# USB_To_UART.net
KiCad netlist of a schematic drawn in Altium Designer
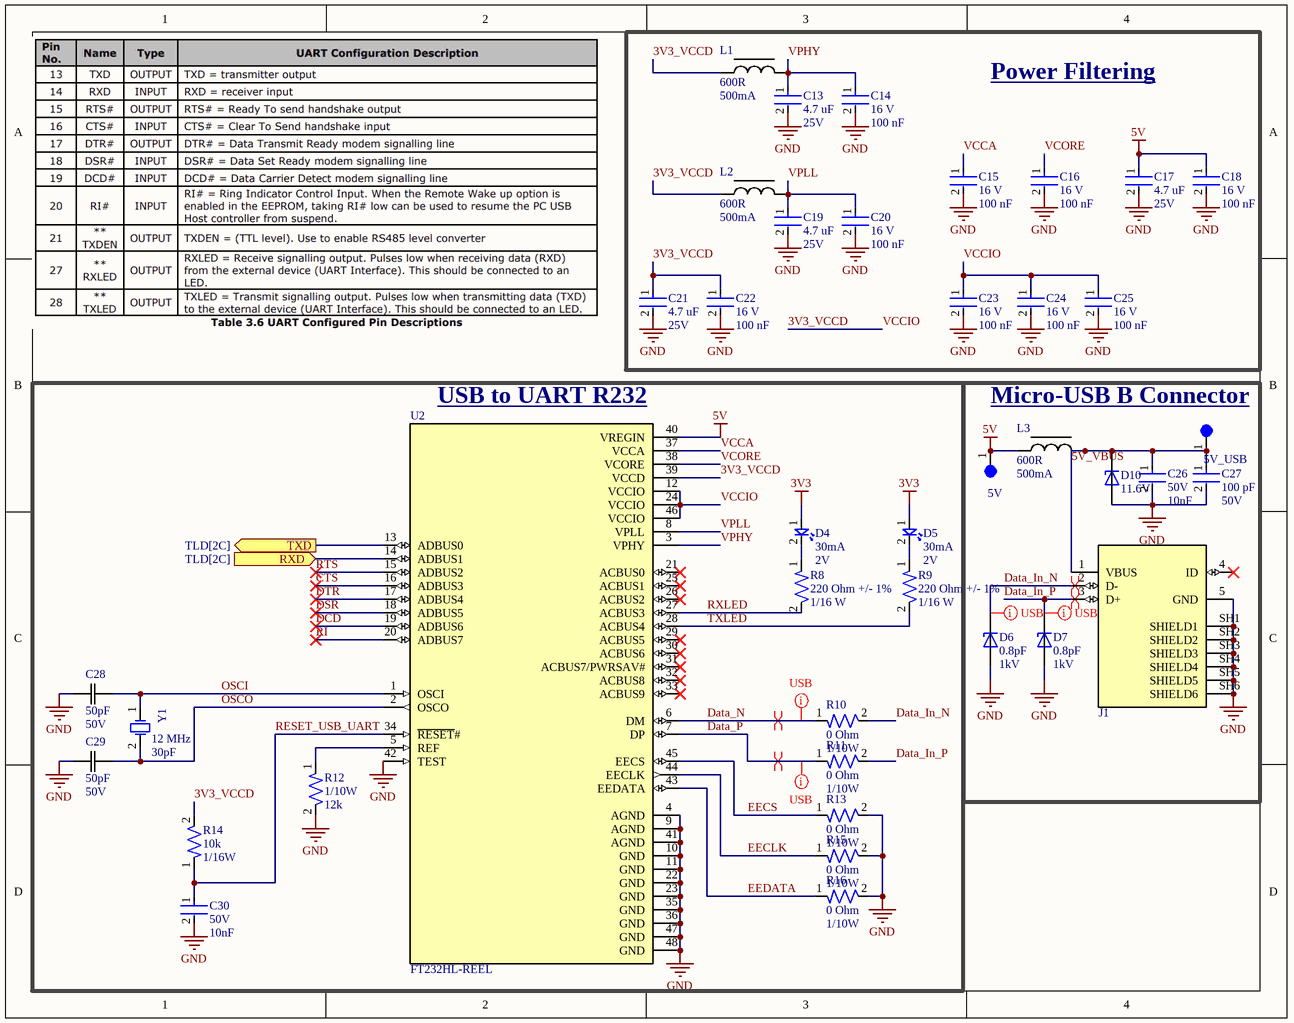
[diagram p0: USB_To_UART.SchDoc]

(export (version "E")
  (design (tool "Eeschema 10.0.6"))
  (components
    (comp (ref "5V")
      (value "5003")
      (footprint "TEST-POINT-0001")
      (description "Oranange PC Test Point, Miniature Phoisphor Bronze Silver Plating Through Hole Mounting Type")
      (libsource (lib "JLC_25") (part "TEST-POINT-0001"))
    )
    (comp (ref "5V_USB")
      (value "5003")
      (footprint "TEST-POINT-0001")
      (description "Oranange PC Test Point, Miniature Phoisphor Bronze Silver Plating Through Hole Mounting Type")
      (libsource (lib "JLC_25") (part "TEST-POINT-0001"))
    )
    (comp (ref "C13")
      (value "CC0603KRX5R8BB475")
      (footprint "CAP-0603")
      (description "CAP CER 4.7UF 25V X5R 0603")
      (fields (field (name "CAPACITANCE") "4.7 uF") (field (name "VOLTAGE") "25V"))
      (libsource (lib "JLC_25") (part "CAP-4.7U-0001"))
    )
    (comp (ref "C14")
      (value "CC0402KRX7R7BB104")
      (footprint "CAP-0402")
      (description "CAP CER 0.1UF 16V X7R 0402")
      (fields (field (name "VOLTAGE RATING") "16 V") (field (name "CAPACITANCE") "100 nF"))
      (libsource (lib "JLC_25") (part "CAP-0.1U-0001"))
    )
    (comp (ref "C15")
      (value "CC0402KRX7R7BB104")
      (footprint "CAP-0402")
      (description "CAP CER 0.1UF 16V X7R 0402")
      (fields (field (name "VOLTAGE RATING") "16 V") (field (name "CAPACITANCE") "100 nF"))
      (libsource (lib "JLC_25") (part "CAP-0.1U-0001"))
    )
    (comp (ref "C16")
      (value "CC0402KRX7R7BB104")
      (footprint "CAP-0402")
      (description "CAP CER 0.1UF 16V X7R 0402")
      (fields (field (name "VOLTAGE RATING") "16 V") (field (name "CAPACITANCE") "100 nF"))
      (libsource (lib "JLC_25") (part "CAP-0.1U-0001"))
    )
    (comp (ref "C17")
      (value "CC0603KRX5R8BB475")
      (footprint "CAP-0603")
      (description "CAP CER 4.7UF 25V X5R 0603")
      (fields (field (name "CAPACITANCE") "4.7 uF") (field (name "VOLTAGE") "25V"))
      (libsource (lib "JLC_25") (part "CAP-4.7U-0001"))
    )
    (comp (ref "C18")
      (value "CC0402KRX7R7BB104")
      (footprint "CAP-0402")
      (description "CAP CER 0.1UF 16V X7R 0402")
      (fields (field (name "VOLTAGE RATING") "16 V") (field (name "CAPACITANCE") "100 nF"))
      (libsource (lib "JLC_25") (part "CAP-0.1U-0001"))
    )
    (comp (ref "C19")
      (value "CC0603KRX5R8BB475")
      (footprint "CAP-0603")
      (description "CAP CER 4.7UF 25V X5R 0603")
      (fields (field (name "CAPACITANCE") "4.7 uF") (field (name "VOLTAGE") "25V"))
      (libsource (lib "JLC_25") (part "CAP-4.7U-0001"))
    )
    (comp (ref "C20")
      (value "CC0402KRX7R7BB104")
      (footprint "CAP-0402")
      (description "CAP CER 0.1UF 16V X7R 0402")
      (fields (field (name "VOLTAGE RATING") "16 V") (field (name "CAPACITANCE") "100 nF"))
      (libsource (lib "JLC_25") (part "CAP-0.1U-0001"))
    )
    (comp (ref "C21")
      (value "CC0603KRX5R8BB475")
      (footprint "CAP-0603")
      (description "CAP CER 4.7UF 25V X5R 0603")
      (fields (field (name "CAPACITANCE") "4.7 uF") (field (name "VOLTAGE") "25V"))
      (libsource (lib "JLC_25") (part "CAP-4.7U-0001"))
    )
    (comp (ref "C22")
      (value "CC0402KRX7R7BB104")
      (footprint "CAP-0402")
      (description "CAP CER 0.1UF 16V X7R 0402")
      (fields (field (name "VOLTAGE RATING") "16 V") (field (name "CAPACITANCE") "100 nF"))
      (libsource (lib "JLC_25") (part "CAP-0.1U-0001"))
    )
    (comp (ref "C23")
      (value "CC0402KRX7R7BB104")
      (footprint "CAP-0402")
      (description "CAP CER 0.1UF 16V X7R 0402")
      (fields (field (name "VOLTAGE RATING") "16 V") (field (name "CAPACITANCE") "100 nF"))
      (libsource (lib "JLC_25") (part "CAP-0.1U-0001"))
    )
    (comp (ref "C24")
      (value "CC0402KRX7R7BB104")
      (footprint "CAP-0402")
      (description "CAP CER 0.1UF 16V X7R 0402")
      (fields (field (name "VOLTAGE RATING") "16 V") (field (name "CAPACITANCE") "100 nF"))
      (libsource (lib "JLC_25") (part "CAP-0.1U-0001"))
    )
    (comp (ref "C25")
      (value "CC0402KRX7R7BB104")
      (footprint "CAP-0402")
      (description "CAP CER 0.1UF 16V X7R 0402")
      (fields (field (name "VOLTAGE RATING") "16 V") (field (name "CAPACITANCE") "100 nF"))
      (libsource (lib "JLC_25") (part "CAP-0.1U-0001"))
    )
    (comp (ref "C26")
      (value "GRM2195C1H103JA01D")
      (footprint "CAP-0805")
      (description "CAP CER 10000PF 50V C0G/NP0 0805")
      (fields (field (name "VOLTAGE") "50V") (field (name "CAPACITANCE") "10nF"))
      (libsource (lib "JLC_25") (part "CAP-10N-0001"))
    )
    (comp (ref "C27")
      (value "CC0402JRNPO9BN101")
      (footprint "CAP-0402")
      (description "CAP CER 100PF 50V C0G/NPO 0402")
      (fields (field (name "CAPACITANCE") "100 pF") (field (name "VOLTAGE") "50V"))
      (libsource (lib "JLC_25") (part "CAP-100P-0001"))
    )
    (comp (ref "C28")
      (value "CC0402JRNPO9BN500")
      (footprint "CAP_CC0402_YAG")
      (description "50 pF ±5% 50V Ceramic Capacitor C0G, NP0 0402 (1005 Metric)")
      (fields
        (field (name "CAPACITANCE") "50pF")
        (field (name "VOLTAGE") "50V")
        (field (name "COPYRIGHT") "Copyright (C) 2025 Ultra Librarian. All rights reserved.")
      )
      (libsource (lib "MasterLib") (part "CAP-50p"))
    )
    (comp (ref "C29")
      (value "CC0402JRNPO9BN500")
      (footprint "CAP_CC0402_YAG")
      (description "50 pF ±5% 50V Ceramic Capacitor C0G, NP0 0402 (1005 Metric)")
      (fields
        (field (name "CAPACITANCE") "50pF")
        (field (name "VOLTAGE") "50V")
        (field (name "COPYRIGHT") "Copyright (C) 2025 Ultra Librarian. All rights reserved.")
      )
      (libsource (lib "MasterLib") (part "CAP-50p"))
    )
    (comp (ref "C30")
      (value "GRM2195C1H103JA01D")
      (footprint "CAP-0805")
      (description "CAP CER 10000PF 50V C0G/NP0 0805")
      (fields (field (name "VOLTAGE") "50V") (field (name "CAPACITANCE") "10nF"))
      (libsource (lib "JLC_25") (part "CAP-10N-0001"))
    )
    (comp (ref "D4")
      (value "BL-HKC36G-AV-TRB")
      (footprint "LED-0603")
      (description "LED YELLOW CLEAR 0603 SMD")
      (fields (field (name "FORWARD CURRENT") "30mA") (field (name "FORWARD VOLTAGE") "2V"))
      (libsource (lib "JLC_25") (part "LED-0001"))
    )
    (comp (ref "D5")
      (value "BL-HKC36G-AV-TRB")
      (footprint "LED-0603")
      (description "LED YELLOW CLEAR 0603 SMD")
      (fields (field (name "FORWARD CURRENT") "30mA") (field (name "FORWARD VOLTAGE") "2V"))
      (libsource (lib "JLC_25") (part "LED-0001"))
    )
    (comp (ref "D6")
      (value "ESD321DPYR")
      (footprint "TVS_ESD321DPYR")
      (description "0.8-pF 3.3-V Â±30-kV ESD protection diode with 6.8-V 16-A TLP clamping in 0402 package for USB 2.0")
      (fields
        (field (name "MF") "Texas Instruments")
        (field (name "CAPACITANCE") "0.8pF")
        (field (name "VOLTAGE") "1kV")
      )
      (libsource (lib "JLC_25") (part "DIO-TVS-0004"))
    )
    (comp (ref "D7")
      (value "ESD321DPYR")
      (footprint "TVS_ESD321DPYR")
      (description "0.8-pF 3.3-V Â±30-kV ESD protection diode with 6.8-V 16-A TLP clamping in 0402 package for USB 2.0")
      (fields
        (field (name "MF") "Texas Instruments")
        (field (name "CAPACITANCE") "0.8pF")
        (field (name "VOLTAGE") "1kV")
      )
      (libsource (lib "JLC_25") (part "DIO-TVS-0004"))
    )
    (comp (ref "D10")
      (value "ESDA7P60-1U1M")
      (footprint "TVS_ESDA7P60-1U1M")
      (description "TVS DIODE 5VWM 11.6VC 1610")
      (fields (field (name "MF") "{'manufacturer': u'STMicroelectronics'}") (field (name "VOLTAGE") "11.6V"))
      (libsource (lib "MasterLib") (part "DIO-TVS-11V"))
    )
    (comp (ref "J1")
      (value "1050170001")
      (footprint "MOLEX_1050170001")
      (description "USB - micro B USB 2.0 Receptacle Connector 5 Position Surface Mount, Right Angle; Through Hole")
      (fields (field (name "MF") "Molex"))
      (libsource (lib "JLC_25") (part "CONN-Micro-USB-B-0001"))
    )
    (comp (ref "L1")
      (value "BLM18AG601SN1D")
      (footprint "FILTER_BLM18AG_MUR-L")
      (description "600 Ohms @ 100 MHz 1 Ferrite Bead 0603 (1608 Metric) 500mA 380mOhm")
      (fields
        (field (name "RESISTANCE") "600R")
        (field (name "CURRENT") "500mA")
        (field (name "COPYRIGHT") "Copyright (C) 2025 Ultra Librarian. All rights reserved.")
      )
      (libsource (lib "JLC_25") (part "FBEAD-600R-0.5A"))
    )
    (comp (ref "L2")
      (value "BLM18AG601SN1D")
      (footprint "FILTER_BLM18AG_MUR-L")
      (description "600 Ohms @ 100 MHz 1 Ferrite Bead 0603 (1608 Metric) 500mA 380mOhm")
      (fields
        (field (name "RESISTANCE") "600R")
        (field (name "CURRENT") "500mA")
        (field (name "COPYRIGHT") "Copyright (C) 2025 Ultra Librarian. All rights reserved.")
      )
      (libsource (lib "JLC_25") (part "FBEAD-600R-0.5A"))
    )
    (comp (ref "L3")
      (value "BLM18AG601SN1D")
      (footprint "FILTER_BLM18AG_MUR-L")
      (description "600 Ohms @ 100 MHz 1 Ferrite Bead 0603 (1608 Metric) 500mA 380mOhm")
      (fields
        (field (name "RESISTANCE") "600R")
        (field (name "CURRENT") "500mA")
        (field (name "COPYRIGHT") "Copyright (C) 2025 Ultra Librarian. All rights reserved.")
      )
      (libsource (lib "JLC_25") (part "FBEAD-600R-0.5A"))
    )
    (comp (ref "R8")
      (value "RM04FTN2200")
      (footprint "RES-0402")
      (fields
        (field (name "JLC PART NUMBER") "C160487")
        (field (name "RESISTANCE") "220 Ohm +/- 1%")
        (field (name "POWER") "1/16 W")
      )
      (libsource (lib "MasterLib") (part "RES-220-0002-JLC"))
    )
    (comp (ref "R9")
      (value "RM04FTN2200")
      (footprint "RES-0402")
      (fields
        (field (name "JLC PART NUMBER") "C160487")
        (field (name "RESISTANCE") "220 Ohm +/- 1%")
        (field (name "POWER") "1/16 W")
      )
      (libsource (lib "MasterLib") (part "RES-220-0002-JLC"))
    )
    (comp (ref "R10")
      (value "RESC1607X60N")
      (footprint "RESC1607X60N")
      (description "0 Ohms Jumper Chip Resistor 0603 (1608 Metric) Moisture Resistant Thick Film")
      (fields
        (field (name "JLC PART NUMBER") "C106231")
        (field (name "RESISTANCE") "0 Ohm")
        (field (name "POWER") "1/10W")
      )
      (libsource (lib "MasterLib") (part "RES-0-0003"))
    )
    (comp (ref "R11")
      (value "RESC1607X60N")
      (footprint "RESC1607X60N")
      (description "0 Ohms Jumper Chip Resistor 0603 (1608 Metric) Moisture Resistant Thick Film")
      (fields
        (field (name "JLC PART NUMBER") "C106231")
        (field (name "RESISTANCE") "0 Ohm")
        (field (name "POWER") "1/10W")
      )
      (libsource (lib "MasterLib") (part "RES-0-0003"))
    )
    (comp (ref "R12")
      (value "RC0603FR-0712KL")
      (footprint "RES-0603")
      (description "RES 12K OHM 1% 1/10W 0603")
      (fields
        (field (name "TOLERANCE") "1%")
        (field (name "POWER") "1/10W")
        (field (name "RESISTANCE") "12k")
      )
      (libsource (lib "JLC_25") (part "RES-12k-0001"))
    )
    (comp (ref "R13")
      (value "RESC1607X60N")
      (footprint "RESC1607X60N")
      (description "0 Ohms Jumper Chip Resistor 0603 (1608 Metric) Moisture Resistant Thick Film")
      (fields
        (field (name "JLC PART NUMBER") "C106231")
        (field (name "RESISTANCE") "0 Ohm")
        (field (name "POWER") "1/10W")
      )
      (libsource (lib "MasterLib") (part "RES-0-0003"))
    )
    (comp (ref "R14")
      (value "RC0402FR-0710KL")
      (footprint "RES-0402")
      (description "RES 10K OHM 1% 1/16W 0402")
      (fields
        (field (name "TOLERANCE") "1%")
        (field (name "RESISTANCE") "10k")
        (field (name "POWER") "1/16W")
      )
      (libsource (lib "JLC_25") (part "RES-10k-0001"))
    )
    (comp (ref "R15")
      (value "RESC1607X60N")
      (footprint "RESC1607X60N")
      (description "0 Ohms Jumper Chip Resistor 0603 (1608 Metric) Moisture Resistant Thick Film")
      (fields
        (field (name "JLC PART NUMBER") "C106231")
        (field (name "RESISTANCE") "0 Ohm")
        (field (name "POWER") "1/10W")
      )
      (libsource (lib "MasterLib") (part "RES-0-0003"))
    )
    (comp (ref "R16")
      (value "RESC1607X60N")
      (footprint "RESC1607X60N")
      (description "0 Ohms Jumper Chip Resistor 0603 (1608 Metric) Moisture Resistant Thick Film")
      (fields
        (field (name "JLC PART NUMBER") "C106231")
        (field (name "RESISTANCE") "0 Ohm")
        (field (name "POWER") "1/10W")
      )
      (libsource (lib "MasterLib") (part "RES-0-0003"))
    )
    (comp (ref "U2")
      (value "FT232HL-REEL")
      (footprint "QFP50P900X900X160-48N")
      (description "Ic, Interface; Usb Hi-Speed To Uart/Fifo/Spi/Jtag, I2c; 1.8v-5.25v; 25ma; Lqfp-48")
      (fields (field (name "MF") "FTDI, Future"))
      (libsource (lib "JLC_25") (part "IC-USB-TO_UART"))
    )
    (comp (ref "Y1")
      (value "830010043")
      (footprint "WE-XTAL_HC49/4HSMX")
      (description "WE-XTAL Quartz Crystal, SMT, HC49/4HSMX, 12 MHz, ±30ppm")
      (fields
        (field (name "MANUFACTURER") "Wurth Elektronik")
        (field (name "FREQUENCY") "12 MHz")
        (field (name "LOAD CAPACITANCE") "30pF")
      )
      (libsource (lib "MasterLib") (part "CRYSTAL-12MHz-30pF"))
    )
  )
  (nets
    (net (code "1") (name "/3V3_VCCD") (class "Default")
      (node (ref "C21") (pin "1") (pinfunction "1_1") (pintype "passive"))
      (node (ref "C22") (pin "1") (pinfunction "1_1") (pintype "passive"))
      (node (ref "C23") (pin "1") (pinfunction "1_1") (pintype "passive"))
      (node (ref "C24") (pin "1") (pinfunction "1_1") (pintype "passive"))
      (node (ref "C25") (pin "1") (pinfunction "1_1") (pintype "passive"))
      (node (ref "L1") (pin "1") (pinfunction "1_1") (pintype "passive"))
      (node (ref "L2") (pin "1") (pinfunction "1_1") (pintype "passive"))
      (node (ref "R14") (pin "2") (pinfunction "2_2") (pintype "passive"))
      (node (ref "U2") (pin "12") (pinfunction "VCCIO_12") (pintype "power_in"))
      (node (ref "U2") (pin "24") (pinfunction "VCCIO_24") (pintype "power_in"))
      (node (ref "U2") (pin "39") (pinfunction "VCCD_39") (pintype "power_in"))
      (node (ref "U2") (pin "46") (pinfunction "VCCIO_46") (pintype "power_in"))
    )
    (net (code "2") (name "/5V_VBUS") (class "Default")
      (node (ref "5V_USB") (pin "1") (pinfunction "0_1") (pintype "passive"))
      (node (ref "C26") (pin "1") (pinfunction "1_1") (pintype "passive"))
      (node (ref "C27") (pin "1") (pinfunction "1_1") (pintype "passive"))
      (node (ref "D10") (pin "1") (pinfunction "1_1") (pintype "passive"))
      (node (ref "J1") (pin "1") (pinfunction "VBUS_1") (pintype "power_in"))
      (node (ref "L3") (pin "2") (pinfunction "2_2") (pintype "passive"))
    )
    (net (code "3") (name "/CTS") (class "Default")
      (node (ref "U2") (pin "16") (pinfunction "ADBUS3_16") (pintype "bidirectional+no_connect"))
    )
    (net (code "4") (name "/DCD") (class "Default")
      (node (ref "U2") (pin "19") (pinfunction "ADBUS6_19") (pintype "bidirectional+no_connect"))
    )
    (net (code "5") (name "/DSR") (class "Default")
      (node (ref "U2") (pin "18") (pinfunction "ADBUS5_18") (pintype "bidirectional+no_connect"))
    )
    (net (code "6") (name "/DTR") (class "Default")
      (node (ref "U2") (pin "17") (pinfunction "ADBUS4_17") (pintype "bidirectional+no_connect"))
    )
    (net (code "7") (name "/Data_In_N") (class "Default")
      (node (ref "D6") (pin "1") (pinfunction "1_1") (pintype "passive"))
      (node (ref "J1") (pin "2") (pinfunction "D-_2") (pintype "bidirectional"))
      (node (ref "R10") (pin "2") (pinfunction "2_2") (pintype "passive"))
    )
    (net (code "8") (name "/Data_In_P") (class "Default")
      (node (ref "D7") (pin "1") (pinfunction "1_1") (pintype "passive"))
      (node (ref "J1") (pin "3") (pinfunction "D+_3") (pintype "bidirectional"))
      (node (ref "R11") (pin "2") (pinfunction "2_2") (pintype "passive"))
    )
    (net (code "9") (name "/Data_N") (class "Default")
      (node (ref "R10") (pin "1") (pinfunction "1_1") (pintype "passive"))
      (node (ref "U2") (pin "6") (pinfunction "DM_6") (pintype "bidirectional"))
    )
    (net (code "10") (name "/Data_P") (class "Default")
      (node (ref "R11") (pin "1") (pinfunction "1_1") (pintype "passive"))
      (node (ref "U2") (pin "7") (pinfunction "DP_7") (pintype "bidirectional"))
    )
    (net (code "11") (name "/EECLK") (class "Default")
      (node (ref "R15") (pin "1") (pinfunction "1_1") (pintype "passive"))
      (node (ref "U2") (pin "44") (pinfunction "EECLK_44") (pintype "output"))
    )
    (net (code "12") (name "/EECS") (class "Default")
      (node (ref "R13") (pin "1") (pinfunction "1_1") (pintype "passive"))
      (node (ref "U2") (pin "45") (pinfunction "EECS_45") (pintype "bidirectional"))
    )
    (net (code "13") (name "/EEDATA") (class "Default")
      (node (ref "R16") (pin "1") (pinfunction "1_1") (pintype "passive"))
      (node (ref "U2") (pin "43") (pinfunction "EEDATA_43") (pintype "bidirectional"))
    )
    (net (code "14") (name "/OSCI") (class "Default")
      (node (ref "C28") (pin "2") (pinfunction "2_2") (pintype "passive"))
      (node (ref "U2") (pin "1") (pinfunction "OSCI_1") (pintype "input"))
      (node (ref "Y1") (pin "1") (pinfunction "OSC1_1") (pintype "passive"))
    )
    (net (code "15") (name "/OSCO") (class "Default")
      (node (ref "C29") (pin "2") (pinfunction "2_2") (pintype "passive"))
      (node (ref "U2") (pin "2") (pinfunction "OSCO_2") (pintype "output"))
      (node (ref "Y1") (pin "2") (pinfunction "OSC2_2") (pintype "passive"))
    )
    (net (code "16") (name "/RESET_USB_UART") (class "Default")
      (node (ref "C30") (pin "1") (pinfunction "1_1") (pintype "passive"))
      (node (ref "R14") (pin "1") (pinfunction "1_1") (pintype "passive"))
      (node (ref "U2") (pin "34") (pinfunction "~{RESET}#_34") (pintype "input"))
    )
    (net (code "17") (name "/RI") (class "Default")
      (node (ref "U2") (pin "20") (pinfunction "ADBUS7_20") (pintype "bidirectional+no_connect"))
    )
    (net (code "18") (name "/RTS") (class "Default")
      (node (ref "U2") (pin "15") (pinfunction "ADBUS2_15") (pintype "bidirectional+no_connect"))
    )
    (net (code "19") (name "/RXD") (class "Default")
      (node (ref "U2") (pin "14") (pinfunction "ADBUS1_14") (pintype "bidirectional"))
    )
    (net (code "20") (name "/RXLED") (class "Default")
      (node (ref "R8") (pin "2") (pinfunction "2_2") (pintype "passive"))
      (node (ref "U2") (pin "27") (pinfunction "ACBUS3_27") (pintype "bidirectional"))
    )
    (net (code "21") (name "/TXD") (class "Default")
      (node (ref "U2") (pin "13") (pinfunction "ADBUS0_13") (pintype "bidirectional"))
    )
    (net (code "22") (name "/TXLED") (class "Default")
      (node (ref "R9") (pin "2") (pinfunction "2_2") (pintype "passive"))
      (node (ref "U2") (pin "28") (pinfunction "ACBUS4_28") (pintype "bidirectional"))
    )
    (net (code "23") (name "/VCCA") (class "Default")
      (node (ref "C15") (pin "1") (pinfunction "1_1") (pintype "passive"))
      (node (ref "U2") (pin "37") (pinfunction "VCCA_37") (pintype "power_in"))
    )
    (net (code "24") (name "/VCORE") (class "Default")
      (node (ref "C16") (pin "1") (pinfunction "1_1") (pintype "passive"))
      (node (ref "U2") (pin "38") (pinfunction "VCORE_38") (pintype "power_in"))
    )
    (net (code "25") (name "/VPHY") (class "Default")
      (node (ref "C13") (pin "1") (pinfunction "1_1") (pintype "passive"))
      (node (ref "C14") (pin "1") (pinfunction "1_1") (pintype "passive"))
      (node (ref "L1") (pin "2") (pinfunction "2_2") (pintype "passive"))
      (node (ref "U2") (pin "3") (pinfunction "VPHY_3") (pintype "power_in"))
    )
    (net (code "26") (name "/VPLL") (class "Default")
      (node (ref "C19") (pin "1") (pinfunction "1_1") (pintype "passive"))
      (node (ref "C20") (pin "1") (pinfunction "1_1") (pintype "passive"))
      (node (ref "L2") (pin "2") (pinfunction "2_2") (pintype "passive"))
      (node (ref "U2") (pin "8") (pinfunction "VPLL_8") (pintype "power_in"))
    )
    (net (code "27") (name "3V3") (class "Default")
      (node (ref "D4") (pin "1") (pinfunction "1_1") (pintype "passive"))
      (node (ref "D5") (pin "1") (pinfunction "1_1") (pintype "passive"))
    )
    (net (code "28") (name "5V") (class "Default")
      (node (ref "5V") (pin "1") (pinfunction "0_1") (pintype "passive"))
      (node (ref "C17") (pin "1") (pinfunction "1_1") (pintype "passive"))
      (node (ref "C18") (pin "1") (pinfunction "1_1") (pintype "passive"))
      (node (ref "L3") (pin "1") (pinfunction "1_1") (pintype "passive"))
      (node (ref "U2") (pin "40") (pinfunction "VREGIN_40") (pintype "power_in"))
    )
    (net (code "29") (name "GND") (class "Default")
      (node (ref "C13") (pin "2") (pinfunction "2_2") (pintype "passive"))
      (node (ref "C14") (pin "2") (pinfunction "2_2") (pintype "passive"))
      (node (ref "C15") (pin "2") (pinfunction "2_2") (pintype "passive"))
      (node (ref "C16") (pin "2") (pinfunction "2_2") (pintype "passive"))
      (node (ref "C17") (pin "2") (pinfunction "2_2") (pintype "passive"))
      (node (ref "C18") (pin "2") (pinfunction "2_2") (pintype "passive"))
      (node (ref "C19") (pin "2") (pinfunction "2_2") (pintype "passive"))
      (node (ref "C20") (pin "2") (pinfunction "2_2") (pintype "passive"))
      (node (ref "C21") (pin "2") (pinfunction "2_2") (pintype "passive"))
      (node (ref "C22") (pin "2") (pinfunction "2_2") (pintype "passive"))
      (node (ref "C23") (pin "2") (pinfunction "2_2") (pintype "passive"))
      (node (ref "C24") (pin "2") (pinfunction "2_2") (pintype "passive"))
      (node (ref "C25") (pin "2") (pinfunction "2_2") (pintype "passive"))
      (node (ref "C26") (pin "2") (pinfunction "2_2") (pintype "passive"))
      (node (ref "C27") (pin "2") (pinfunction "2_2") (pintype "passive"))
      (node (ref "C28") (pin "1") (pinfunction "1_1") (pintype "passive"))
      (node (ref "C29") (pin "1") (pinfunction "1_1") (pintype "passive"))
      (node (ref "C30") (pin "2") (pinfunction "2_2") (pintype "passive"))
      (node (ref "D10") (pin "2") (pinfunction "2_2") (pintype "passive"))
      (node (ref "D6") (pin "2") (pinfunction "2_2") (pintype "passive"))
      (node (ref "D7") (pin "2") (pinfunction "2_2") (pintype "passive"))
      (node (ref "J1") (pin "5") (pinfunction "GND_5") (pintype "power_in"))
      (node (ref "J1") (pin "SH1") (pinfunction "SHIELD1_SH1") (pintype "passive"))
      (node (ref "J1") (pin "SH2") (pinfunction "SHIELD2_SH2") (pintype "passive"))
      (node (ref "J1") (pin "SH3") (pinfunction "SHIELD3_SH3") (pintype "passive"))
      (node (ref "J1") (pin "SH4") (pinfunction "SHIELD4_SH4") (pintype "passive"))
      (node (ref "J1") (pin "SH5") (pinfunction "SHIELD5_SH5") (pintype "passive"))
      (node (ref "J1") (pin "SH6") (pinfunction "SHIELD6_SH6") (pintype "passive"))
      (node (ref "R12") (pin "2") (pinfunction "2_2") (pintype "passive"))
      (node (ref "R13") (pin "2") (pinfunction "2_2") (pintype "passive"))
      (node (ref "R15") (pin "2") (pinfunction "2_2") (pintype "passive"))
      (node (ref "R16") (pin "2") (pinfunction "2_2") (pintype "passive"))
      (node (ref "U2") (pin "10") (pinfunction "GND_10") (pintype "power_in"))
      (node (ref "U2") (pin "11") (pinfunction "GND_11") (pintype "power_in"))
      (node (ref "U2") (pin "22") (pinfunction "GND_22") (pintype "power_in"))
      (node (ref "U2") (pin "23") (pinfunction "GND_23") (pintype "power_in"))
      (node (ref "U2") (pin "35") (pinfunction "GND_35") (pintype "power_in"))
      (node (ref "U2") (pin "36") (pinfunction "GND_36") (pintype "power_in"))
      (node (ref "U2") (pin "4") (pinfunction "AGND_4") (pintype "power_in"))
      (node (ref "U2") (pin "41") (pinfunction "AGND_41") (pintype "power_in"))
      (node (ref "U2") (pin "42") (pinfunction "TEST_42") (pintype "input"))
      (node (ref "U2") (pin "47") (pinfunction "GND_47") (pintype "power_in"))
      (node (ref "U2") (pin "48") (pinfunction "GND_48") (pintype "power_in"))
      (node (ref "U2") (pin "9") (pinfunction "AGND_9") (pintype "power_in"))
    )
    (net (code "30") (name "Net-(D4-Pad2)") (class "Default")
      (node (ref "D4") (pin "2") (pinfunction "2_2") (pintype "passive"))
      (node (ref "R8") (pin "1") (pinfunction "1_1") (pintype "passive"))
    )
    (net (code "31") (name "Net-(D5-Pad2)") (class "Default")
      (node (ref "D5") (pin "2") (pinfunction "2_2") (pintype "passive"))
      (node (ref "R9") (pin "1") (pinfunction "1_1") (pintype "passive"))
    )
    (net (code "32") (name "Net-(U2-REF)") (class "Default")
      (node (ref "R12") (pin "1") (pinfunction "1_1") (pintype "passive"))
      (node (ref "U2") (pin "5") (pinfunction "REF_5") (pintype "input"))
    )
    (net (code "33") (name "unconnected-(J1-ID-Pad4)") (class "Default")
      (node (ref "J1") (pin "4") (pinfunction "ID_4") (pintype "bidirectional+no_connect"))
    )
    (net (code "34") (name "unconnected-(U2-ACBUS0-Pad21)") (class "Default")
      (node (ref "U2") (pin "21") (pinfunction "ACBUS0_21") (pintype "bidirectional+no_connect"))
    )
    (net (code "35") (name "unconnected-(U2-ACBUS1-Pad25)") (class "Default")
      (node (ref "U2") (pin "25") (pinfunction "ACBUS1_25") (pintype "bidirectional+no_connect"))
    )
    (net (code "36") (name "unconnected-(U2-ACBUS2-Pad26)") (class "Default")
      (node (ref "U2") (pin "26") (pinfunction "ACBUS2_26") (pintype "bidirectional+no_connect"))
    )
    (net (code "37") (name "unconnected-(U2-ACBUS5-Pad29)") (class "Default")
      (node (ref "U2") (pin "29") (pinfunction "ACBUS5_29") (pintype "bidirectional+no_connect"))
    )
    (net (code "38") (name "unconnected-(U2-ACBUS6-Pad30)") (class "Default")
      (node (ref "U2") (pin "30") (pinfunction "ACBUS6_30") (pintype "bidirectional+no_connect"))
    )
    (net (code "39") (name "unconnected-(U2-ACBUS7{slash}PWRSAV#-Pad31)") (class "Default")
      (node (ref "U2") (pin "31") (pinfunction "ACBUS7/PWRSAV#_31") (pintype "bidirectional+no_connect"))
    )
    (net (code "40") (name "unconnected-(U2-ACBUS8-Pad32)") (class "Default")
      (node (ref "U2") (pin "32") (pinfunction "ACBUS8_32") (pintype "bidirectional+no_connect"))
    )
    (net (code "41") (name "unconnected-(U2-ACBUS9-Pad33)") (class "Default")
      (node (ref "U2") (pin "33") (pinfunction "ACBUS9_33") (pintype "bidirectional+no_connect"))
    )
  )
)
